# Sheet2.net
KiCad netlist of a schematic drawn in Altium Designer
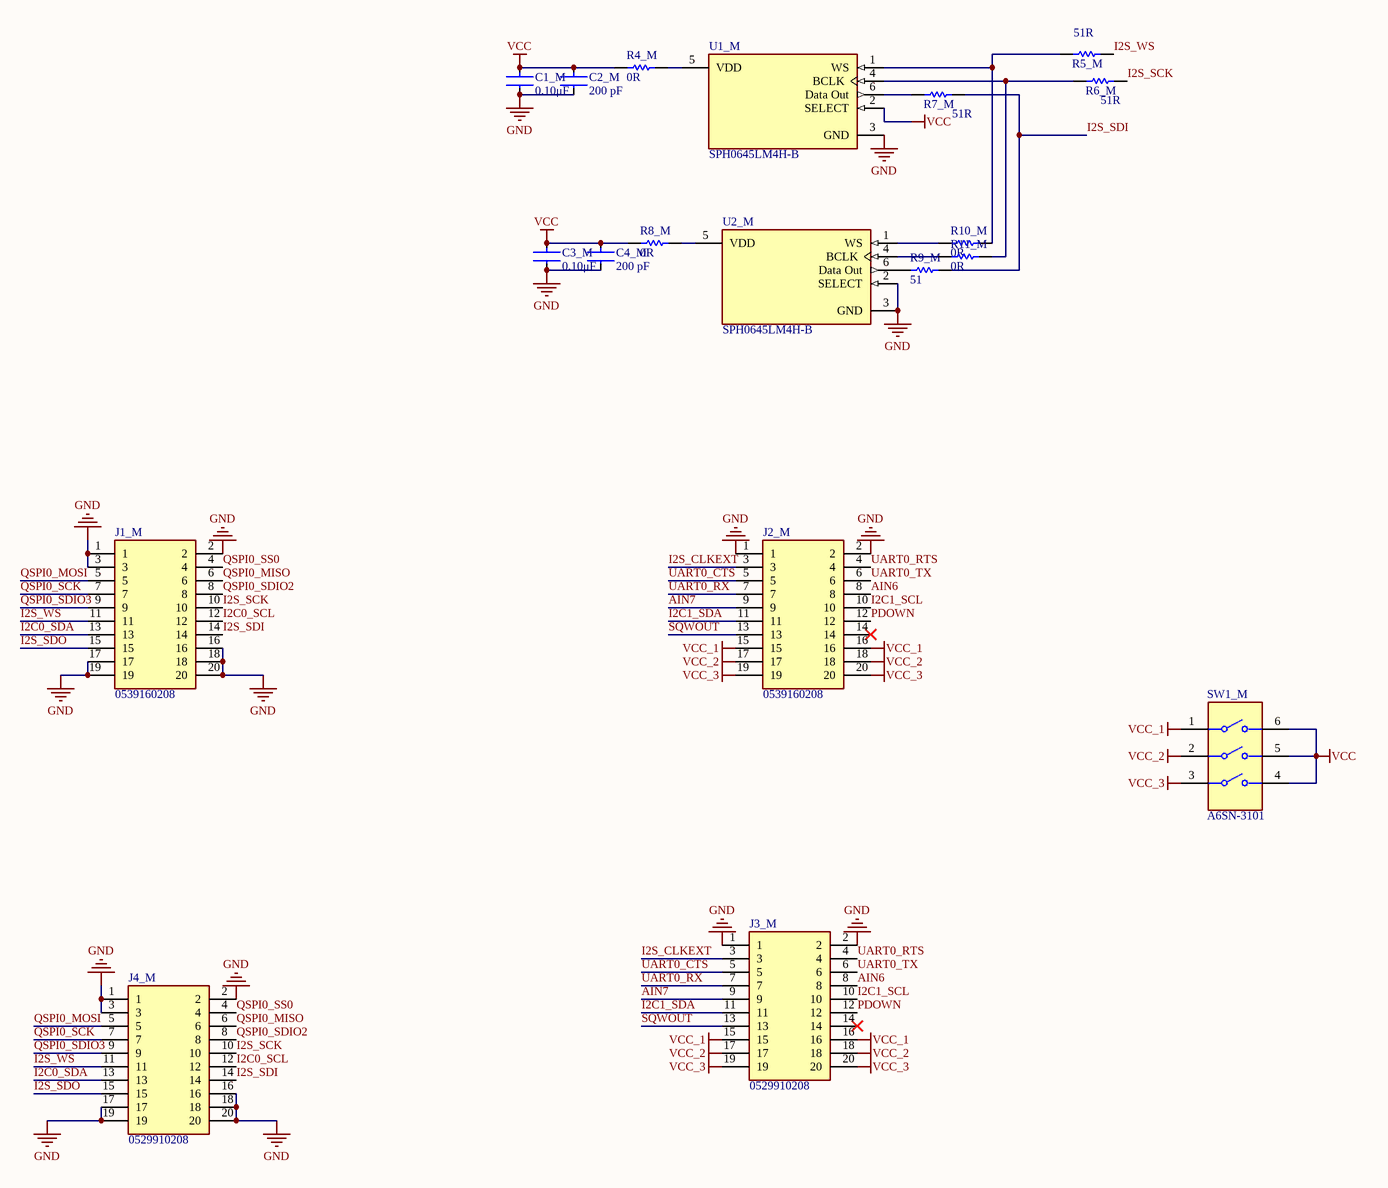
[diagram p0: Sheet2.SchDoc]

(export (version "E")
  (design (tool "Eeschema 10.0.6"))
  (components
    (comp (ref "C1_M")
      (value "GRM155R71C104KA88D")
      (footprint "FP-GRM15-MFG")
      (description "CAP CER 0.1UF 16V X7R 0402")
      (fields
        (field (name "TOLERANCE") "10%")
        (field (name "OCTOPART") "https://octopart.com/grm155r71c104ka88d-murata-196880")
        (field (name "CAPACITANCE") "0.10μF")
      )
      (libsource (lib "Altium Content Vault") (part "236180d848d6139a670b325ea6854c9"))
    )
    (comp (ref "C2_M")
      (value "C0402C201J5GACTU")
      (footprint "FP-C0402-BB-MFG")
      (description "CAP CER 200PF 50V NP0 0402")
      (fields
        (field (name "OCTOPART") "https://octopart.com/c0402c201j5gactu-kemet-19049754")
        (field (name "CAPACITANCE") "200 pF")
        (field (name "MANUFACTURER") "Kemet")
      )
      (libsource (lib "Altium Content Vault") (part "b4654b650e69147ec39a6b967a45e02"))
    )
    (comp (ref "C3_M")
      (value "GRM155R71C104KA88D")
      (footprint "FP-GRM15-MFG")
      (description "CAP CER 0.1UF 16V X7R 0402")
      (fields
        (field (name "TOLERANCE") "10%")
        (field (name "OCTOPART") "https://octopart.com/grm155r71c104ka88d-murata-196880")
        (field (name "CAPACITANCE") "0.10μF")
      )
      (libsource (lib "Altium Content Vault") (part "236180d848d6139a670b325ea6854c9"))
    )
    (comp (ref "C4_M")
      (value "C0402C201J5GACTU")
      (footprint "FP-C0402-BB-MFG")
      (description "CAP CER 200PF 50V NP0 0402")
      (fields
        (field (name "OCTOPART") "https://octopart.com/c0402c201j5gactu-kemet-19049754")
        (field (name "CAPACITANCE") "200 pF")
        (field (name "MANUFACTURER") "Kemet")
      )
      (libsource (lib "Altium Content Vault") (part "b4654b650e69147ec39a6b967a45e02"))
    )
    (comp (ref "J1_M")
      (value "0539160208")
      (footprint "MOLEX-  539160208")
      (libsource (lib "52991-0208") (part "53916-0208"))
    )
    (comp (ref "J2_M")
      (value "0539160208")
      (footprint "MOLEX-  539160208")
      (libsource (lib "52991-0208") (part "53916-0208"))
    )
    (comp (ref "J3_M")
      (value "0529910208")
      (footprint "MOLEX_52991-0208")
      (description "20 Position Connector Receptacle, Center Strip Contacts Surface Mount Gold")
      (fields (field (name "MP") "52991-0208") (field (name "MF") "Molex"))
      (libsource (lib "52991-0208") (part "52991-0208"))
    )
    (comp (ref "J4_M")
      (value "0529910208")
      (footprint "MOLEX_52991-0208")
      (description "20 Position Connector Receptacle, Center Strip Contacts Surface Mount Gold")
      (fields (field (name "MP") "52991-0208") (field (name "MF") "Molex"))
      (libsource (lib "52991-0208") (part "52991-0208"))
    )
    (comp (ref "R4_M")
      (value "0R")
      (footprint "RESC1005X40X25NL05T10")
      (fields (field (name "MANUFACTURER") "Yageo / Phycomp") (field (name "PART NUMBER") "RC0402JR-070RL"))
      (libsource (lib "Altium Content Vault") (part "RES"))
    )
    (comp (ref "R5_M")
      (value "51R")
      (footprint "RESC1005X40X25LL05T05")
      (fields (field (name "MANUFACTURER") "Panasonic") (field (name "PART NUMBER") "ERJ-2RKF51R0X"))
      (libsource (lib "Altium Content Vault") (part "RES"))
    )
    (comp (ref "R6_M")
      (value "51R")
      (footprint "RESC1005X40X25LL05T05")
      (fields (field (name "MANUFACTURER") "Panasonic") (field (name "PART NUMBER") "ERJ-2RKF51R0X"))
      (libsource (lib "Altium Content Vault") (part "RES"))
    )
    (comp (ref "R7_M")
      (value "51R")
      (footprint "RESC1005X40X25LL05T05")
      (fields (field (name "MANUFACTURER") "Panasonic") (field (name "PART NUMBER") "ERJ-2RKF51R0X"))
      (libsource (lib "Altium Content Vault") (part "RES"))
    )
    (comp (ref "R8_M")
      (value "0R")
      (footprint "RESC1005X40X25NL05T10")
      (fields (field (name "MANUFACTURER") "Yageo / Phycomp") (field (name "PART NUMBER") "RC0402JR-070RL"))
      (libsource (lib "Altium Content Vault") (part "RES"))
    )
    (comp (ref "R9_M")
      (value "51")
      (footprint "RESC1005X40X25LL05T05")
      (fields (field (name "MANUFACTURER") "Panasonic") (field (name "PART NUMBER") "ERJ-2RKF51R0X"))
      (libsource (lib "Altium Content Vault") (part "RES"))
    )
    (comp (ref "R10_M")
      (value "0R")
      (footprint "RESC1005X40X25NL05T10")
      (fields (field (name "MANUFACTURER") "Yageo / Phycomp") (field (name "PART NUMBER") "RC0402JR-070RL"))
      (libsource (lib "Altium Content Vault") (part "RES"))
    )
    (comp (ref "R11_M")
      (value "0R")
      (footprint "RESC1005X40X25NL05T10")
      (fields (field (name "MANUFACTURER") "Yageo / Phycomp") (field (name "PART NUMBER") "RC0402JR-070RL"))
      (libsource (lib "Altium Content Vault") (part "RES"))
    )
    (comp (ref "SW1_M")
      (value "A6SN-3101")
      (footprint "FP-A6SN-3101-MFG")
      (description "SWITCH SLIDE DIP SPST 25MA 24V")
      (fields
        (field (name "MANUFACTURER") "Omron Electronics Inc-EMC Div")
        (field (name "OCTOPART") "https://octopart.com/a6sn-3101-omron-55396000")
      )
      (libsource (lib "Altium Content Vault") (part "c5ed29025a0a80be921a75429a93ff4"))
    )
    (comp (ref "U1_M")
      (value "SPH0645LM4H-B")
      (footprint "FP-SPH0645LM4H-B-MFG")
      (description "MICROPHONE MEMS DIGITAL I2S OMNI")
      (libsource (lib "Altium Content Vault") (part "00dabddac7b84e9f2d22fc00757709e"))
    )
    (comp (ref "U2_M")
      (value "SPH0645LM4H-B")
      (footprint "FP-SPH0645LM4H-B-MFG")
      (description "MICROPHONE MEMS DIGITAL I2S OMNI")
      (libsource (lib "Altium Content Vault") (part "00dabddac7b84e9f2d22fc00757709e"))
    )
  )
  (nets
    (net (code "1") (name "/AIN6") (class "Default")
      (node (ref "J2_M") (pin "8") (pinfunction "8_8") (pintype "passive"))
      (node (ref "J3_M") (pin "8") (pinfunction "8_8") (pintype "passive"))
    )
    (net (code "2") (name "/AIN7") (class "Default")
      (node (ref "J2_M") (pin "9") (pinfunction "9_9") (pintype "passive"))
      (node (ref "J3_M") (pin "9") (pinfunction "9_9") (pintype "passive"))
    )
    (net (code "3") (name "/I2C0_SCL") (class "Default")
      (node (ref "J1_M") (pin "12") (pinfunction "12_12") (pintype "passive"))
      (node (ref "J4_M") (pin "12") (pinfunction "12_12") (pintype "passive"))
    )
    (net (code "4") (name "/I2C0_SDA") (class "Default")
      (node (ref "J1_M") (pin "13") (pinfunction "13_13") (pintype "passive"))
      (node (ref "J4_M") (pin "13") (pinfunction "13_13") (pintype "passive"))
    )
    (net (code "5") (name "/I2C1_SCL") (class "Default")
      (node (ref "J2_M") (pin "10") (pinfunction "10_10") (pintype "passive"))
      (node (ref "J3_M") (pin "10") (pinfunction "10_10") (pintype "passive"))
    )
    (net (code "6") (name "/I2C1_SDA") (class "Default")
      (node (ref "J2_M") (pin "11") (pinfunction "11_11") (pintype "passive"))
      (node (ref "J3_M") (pin "11") (pinfunction "11_11") (pintype "passive"))
    )
    (net (code "7") (name "/I2S_CLKEXT") (class "Default")
      (node (ref "J2_M") (pin "3") (pinfunction "3_3") (pintype "passive"))
      (node (ref "J3_M") (pin "3") (pinfunction "3_3") (pintype "passive"))
    )
    (net (code "8") (name "/I2S_SCK") (class "Default")
      (node (ref "J1_M") (pin "10") (pinfunction "10_10") (pintype "passive"))
      (node (ref "J4_M") (pin "10") (pinfunction "10_10") (pintype "passive"))
      (node (ref "R6_M") (pin "2") (pinfunction "2_2") (pintype "passive"))
    )
    (net (code "9") (name "/I2S_SDI") (class "Default")
      (node (ref "J1_M") (pin "14") (pinfunction "14_14") (pintype "passive"))
      (node (ref "J4_M") (pin "14") (pinfunction "14_14") (pintype "passive"))
      (node (ref "R7_M") (pin "2") (pinfunction "2_2") (pintype "passive"))
      (node (ref "R9_M") (pin "2") (pinfunction "2_2") (pintype "passive"))
    )
    (net (code "10") (name "/I2S_SDO") (class "Default")
      (node (ref "J1_M") (pin "15") (pinfunction "15_15") (pintype "passive"))
      (node (ref "J4_M") (pin "15") (pinfunction "15_15") (pintype "passive"))
    )
    (net (code "11") (name "/I2S_WS") (class "Default")
      (node (ref "J1_M") (pin "11") (pinfunction "11_11") (pintype "passive"))
      (node (ref "J4_M") (pin "11") (pinfunction "11_11") (pintype "passive"))
      (node (ref "R5_M") (pin "2") (pinfunction "2_2") (pintype "passive"))
    )
    (net (code "12") (name "/PDOWN") (class "Default")
      (node (ref "J2_M") (pin "12") (pinfunction "12_12") (pintype "passive"))
      (node (ref "J3_M") (pin "12") (pinfunction "12_12") (pintype "passive"))
    )
    (net (code "13") (name "/QSPI0_MISO") (class "Default")
      (node (ref "J1_M") (pin "6") (pinfunction "6_6") (pintype "passive"))
      (node (ref "J4_M") (pin "6") (pinfunction "6_6") (pintype "passive"))
    )
    (net (code "14") (name "/QSPI0_MOSI") (class "Default")
      (node (ref "J1_M") (pin "5") (pinfunction "5_5") (pintype "passive"))
      (node (ref "J4_M") (pin "5") (pinfunction "5_5") (pintype "passive"))
    )
    (net (code "15") (name "/QSPI0_SCK") (class "Default")
      (node (ref "J1_M") (pin "7") (pinfunction "7_7") (pintype "passive"))
      (node (ref "J4_M") (pin "7") (pinfunction "7_7") (pintype "passive"))
    )
    (net (code "16") (name "/QSPI0_SDIO2") (class "Default")
      (node (ref "J1_M") (pin "8") (pinfunction "8_8") (pintype "passive"))
      (node (ref "J4_M") (pin "8") (pinfunction "8_8") (pintype "passive"))
    )
    (net (code "17") (name "/QSPI0_SDIO3") (class "Default")
      (node (ref "J1_M") (pin "9") (pinfunction "9_9") (pintype "passive"))
      (node (ref "J4_M") (pin "9") (pinfunction "9_9") (pintype "passive"))
    )
    (net (code "18") (name "/QSPI0_SS0") (class "Default")
      (node (ref "J1_M") (pin "4") (pinfunction "4_4") (pintype "passive"))
      (node (ref "J4_M") (pin "4") (pinfunction "4_4") (pintype "passive"))
    )
    (net (code "19") (name "/SQWOUT") (class "Default")
      (node (ref "J2_M") (pin "13") (pinfunction "13_13") (pintype "passive"))
      (node (ref "J3_M") (pin "13") (pinfunction "13_13") (pintype "passive"))
    )
    (net (code "20") (name "/UART0_CTS") (class "Default")
      (node (ref "J2_M") (pin "5") (pinfunction "5_5") (pintype "passive"))
      (node (ref "J3_M") (pin "5") (pinfunction "5_5") (pintype "passive"))
    )
    (net (code "21") (name "/UART0_RTS") (class "Default")
      (node (ref "J2_M") (pin "4") (pinfunction "4_4") (pintype "passive"))
      (node (ref "J3_M") (pin "4") (pinfunction "4_4") (pintype "passive"))
    )
    (net (code "22") (name "/UART0_RX") (class "Default")
      (node (ref "J2_M") (pin "7") (pinfunction "7_7") (pintype "passive"))
      (node (ref "J3_M") (pin "7") (pinfunction "7_7") (pintype "passive"))
    )
    (net (code "23") (name "/UART0_TX") (class "Default")
      (node (ref "J2_M") (pin "6") (pinfunction "6_6") (pintype "passive"))
      (node (ref "J3_M") (pin "6") (pinfunction "6_6") (pintype "passive"))
    )
    (net (code "24") (name "GND") (class "Default")
      (node (ref "C1_M") (pin "1") (pinfunction "1_1") (pintype "passive"))
      (node (ref "C2_M") (pin "2") (pinfunction "2_2") (pintype "passive"))
      (node (ref "C3_M") (pin "1") (pinfunction "1_1") (pintype "passive"))
      (node (ref "C4_M") (pin "2") (pinfunction "2_2") (pintype "passive"))
      (node (ref "J1_M") (pin "1") (pinfunction "1_1") (pintype "passive"))
      (node (ref "J1_M") (pin "16") (pinfunction "16_16") (pintype "passive"))
      (node (ref "J1_M") (pin "17") (pinfunction "17_17") (pintype "passive"))
      (node (ref "J1_M") (pin "18") (pinfunction "18_18") (pintype "passive"))
      (node (ref "J1_M") (pin "19") (pinfunction "19_19") (pintype "passive"))
      (node (ref "J1_M") (pin "2") (pinfunction "2_2") (pintype "passive"))
      (node (ref "J1_M") (pin "20") (pinfunction "20_20") (pintype "passive"))
      (node (ref "J1_M") (pin "3") (pinfunction "3_3") (pintype "passive"))
      (node (ref "J2_M") (pin "1") (pinfunction "1_1") (pintype "passive"))
      (node (ref "J2_M") (pin "2") (pinfunction "2_2") (pintype "passive"))
      (node (ref "J3_M") (pin "1") (pinfunction "1_1") (pintype "passive"))
      (node (ref "J3_M") (pin "2") (pinfunction "2_2") (pintype "passive"))
      (node (ref "J4_M") (pin "1") (pinfunction "1_1") (pintype "passive"))
      (node (ref "J4_M") (pin "16") (pinfunction "16_16") (pintype "passive"))
      (node (ref "J4_M") (pin "17") (pinfunction "17_17") (pintype "passive"))
      (node (ref "J4_M") (pin "18") (pinfunction "18_18") (pintype "passive"))
      (node (ref "J4_M") (pin "19") (pinfunction "19_19") (pintype "passive"))
      (node (ref "J4_M") (pin "2") (pinfunction "2_2") (pintype "passive"))
      (node (ref "J4_M") (pin "20") (pinfunction "20_20") (pintype "passive"))
      (node (ref "J4_M") (pin "3") (pinfunction "3_3") (pintype "passive"))
      (node (ref "U1_M") (pin "3") (pinfunction "GND_3") (pintype "power_in"))
      (node (ref "U2_M") (pin "2") (pinfunction "SELECT_2") (pintype "input"))
      (node (ref "U2_M") (pin "3") (pinfunction "GND_3") (pintype "power_in"))
    )
    (net (code "25") (name "Net-(U1_M-BCLK)") (class "Default")
      (node (ref "R11_M") (pin "2") (pinfunction "2_2") (pintype "passive"))
      (node (ref "R6_M") (pin "1") (pinfunction "1_1") (pintype "passive"))
      (node (ref "U1_M") (pin "4") (pinfunction "BCLK_4") (pintype "input"))
    )
    (net (code "26") (name "Net-(U1_M-Data_Out)") (class "Default")
      (node (ref "R7_M") (pin "1") (pinfunction "1_1") (pintype "passive"))
      (node (ref "U1_M") (pin "6") (pinfunction "Data_Out_6") (pintype "output"))
    )
    (net (code "27") (name "Net-(U1_M-VDD)") (class "Default")
      (node (ref "R4_M") (pin "2") (pinfunction "2_2") (pintype "passive"))
      (node (ref "U1_M") (pin "5") (pinfunction "VDD_5") (pintype "power_in"))
    )
    (net (code "28") (name "Net-(U1_M-WS)") (class "Default")
      (node (ref "R10_M") (pin "2") (pinfunction "2_2") (pintype "passive"))
      (node (ref "R5_M") (pin "1") (pinfunction "1_1") (pintype "passive"))
      (node (ref "U1_M") (pin "1") (pinfunction "WS_1") (pintype "input"))
    )
    (net (code "29") (name "Net-(U2_M-BCLK)") (class "Default")
      (node (ref "R11_M") (pin "1") (pinfunction "1_1") (pintype "passive"))
      (node (ref "U2_M") (pin "4") (pinfunction "BCLK_4") (pintype "input"))
    )
    (net (code "30") (name "Net-(U2_M-Data_Out)") (class "Default")
      (node (ref "R9_M") (pin "1") (pinfunction "1_1") (pintype "passive"))
      (node (ref "U2_M") (pin "6") (pinfunction "Data_Out_6") (pintype "output"))
    )
    (net (code "31") (name "Net-(U2_M-VDD)") (class "Default")
      (node (ref "R8_M") (pin "2") (pinfunction "2_2") (pintype "passive"))
      (node (ref "U2_M") (pin "5") (pinfunction "VDD_5") (pintype "power_in"))
    )
    (net (code "32") (name "Net-(U2_M-WS)") (class "Default")
      (node (ref "R10_M") (pin "1") (pinfunction "1_1") (pintype "passive"))
      (node (ref "U2_M") (pin "1") (pinfunction "WS_1") (pintype "input"))
    )
    (net (code "33") (name "VCC") (class "Default")
      (node (ref "C1_M") (pin "2") (pinfunction "2_2") (pintype "passive"))
      (node (ref "C2_M") (pin "1") (pinfunction "1_1") (pintype "passive"))
      (node (ref "C3_M") (pin "2") (pinfunction "2_2") (pintype "passive"))
      (node (ref "C4_M") (pin "1") (pinfunction "1_1") (pintype "passive"))
      (node (ref "R4_M") (pin "1") (pinfunction "1_1") (pintype "passive"))
      (node (ref "R8_M") (pin "1") (pinfunction "1_1") (pintype "passive"))
      (node (ref "SW1_M") (pin "4") (pinfunction "4_4") (pintype "passive"))
      (node (ref "SW1_M") (pin "5") (pinfunction "5_5") (pintype "passive"))
      (node (ref "SW1_M") (pin "6") (pinfunction "6_6") (pintype "passive"))
      (node (ref "U1_M") (pin "2") (pinfunction "SELECT_2") (pintype "input"))
    )
    (net (code "34") (name "VCC_1") (class "Default")
      (node (ref "J2_M") (pin "15") (pinfunction "15_15") (pintype "passive"))
      (node (ref "J2_M") (pin "16") (pinfunction "16_16") (pintype "passive"))
      (node (ref "J3_M") (pin "15") (pinfunction "15_15") (pintype "passive"))
      (node (ref "J3_M") (pin "16") (pinfunction "16_16") (pintype "passive"))
      (node (ref "SW1_M") (pin "1") (pinfunction "1_1") (pintype "passive"))
    )
    (net (code "35") (name "VCC_2") (class "Default")
      (node (ref "J2_M") (pin "17") (pinfunction "17_17") (pintype "passive"))
      (node (ref "J2_M") (pin "18") (pinfunction "18_18") (pintype "passive"))
      (node (ref "J3_M") (pin "17") (pinfunction "17_17") (pintype "passive"))
      (node (ref "J3_M") (pin "18") (pinfunction "18_18") (pintype "passive"))
      (node (ref "SW1_M") (pin "2") (pinfunction "2_2") (pintype "passive"))
    )
    (net (code "36") (name "VCC_3") (class "Default")
      (node (ref "J2_M") (pin "19") (pinfunction "19_19") (pintype "passive"))
      (node (ref "J2_M") (pin "20") (pinfunction "20_20") (pintype "passive"))
      (node (ref "J3_M") (pin "19") (pinfunction "19_19") (pintype "passive"))
      (node (ref "J3_M") (pin "20") (pinfunction "20_20") (pintype "passive"))
      (node (ref "SW1_M") (pin "3") (pinfunction "3_3") (pintype "passive"))
    )
    (net (code "37") (name "unconnected-(J2_M-Pad14)") (class "Default")
      (node (ref "J2_M") (pin "14") (pinfunction "14_14") (pintype "passive+no_connect"))
    )
    (net (code "38") (name "unconnected-(J3_M-Pad14)") (class "Default")
      (node (ref "J3_M") (pin "14") (pinfunction "14_14") (pintype "passive+no_connect"))
    )
  )
)
